# Rocky_Switch_SSR_Shield.net
KiCad netlist of a schematic drawn in EAGLE
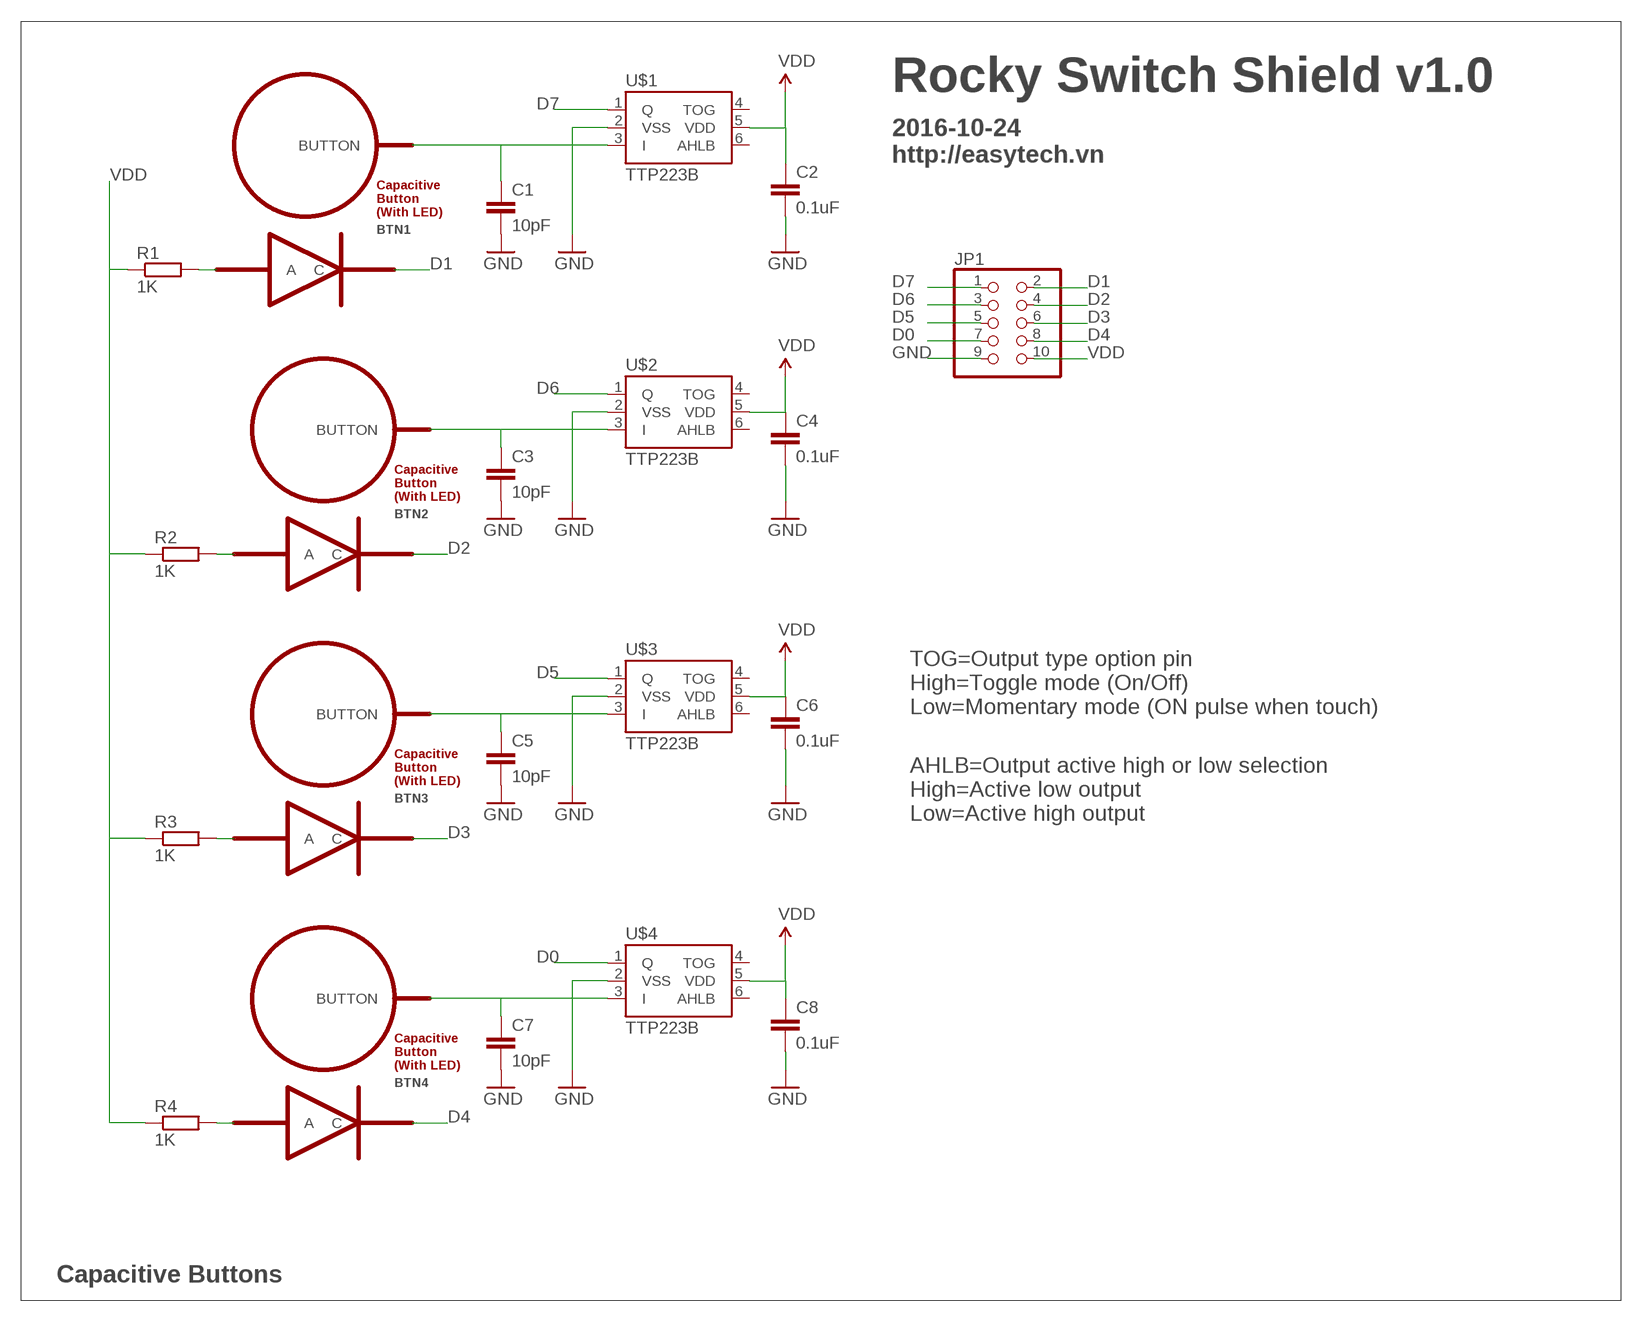
[diagram p0: schematic, sheet 1]

(export (version "E")
  (design (tool "Eeschema 10.0.6"))
  (components
    (comp (ref "BTN1")
      (value "BUTTON_PASSIVE_LED")
      (footprint "eagle-import:BUTTON_PASSIVE_LED")
      (libsource (lib "eagle-import") (part "BUTTON_PASSIVE_LED"))
    )
    (comp (ref "BTN2")
      (value "BUTTON_PASSIVE_LED")
      (footprint "eagle-import:BUTTON_PASSIVE_LED")
      (libsource (lib "eagle-import") (part "BUTTON_PASSIVE_LED"))
    )
    (comp (ref "BTN3")
      (value "BUTTON_PASSIVE_LED")
      (footprint "eagle-import:BUTTON_PASSIVE_LED")
      (libsource (lib "eagle-import") (part "BUTTON_PASSIVE_LED"))
    )
    (comp (ref "BTN4")
      (value "BUTTON_PASSIVE_LED")
      (footprint "eagle-import:BUTTON_PASSIVE_LED")
      (libsource (lib "eagle-import") (part "BUTTON_PASSIVE_LED"))
    )
    (comp (ref "C1")
      (value "10pF")
      (footprint "eagle-import:C0805K")
      (libsource (lib "eagle-import") (part "C-EUC0805K"))
    )
    (comp (ref "C2")
      (value "0.1uF")
      (footprint "eagle-import:C0805K")
      (libsource (lib "eagle-import") (part "C-EUC0805K"))
    )
    (comp (ref "C3")
      (value "10pF")
      (footprint "eagle-import:C0805K")
      (libsource (lib "eagle-import") (part "C-EUC0805K"))
    )
    (comp (ref "C4")
      (value "0.1uF")
      (footprint "eagle-import:C0805K")
      (libsource (lib "eagle-import") (part "C-EUC0805K"))
    )
    (comp (ref "C5")
      (value "10pF")
      (footprint "eagle-import:C0805K")
      (libsource (lib "eagle-import") (part "C-EUC0805K"))
    )
    (comp (ref "C6")
      (value "0.1uF")
      (footprint "eagle-import:C0805K")
      (libsource (lib "eagle-import") (part "C-EUC0805K"))
    )
    (comp (ref "C7")
      (value "10pF")
      (footprint "eagle-import:C0805K")
      (libsource (lib "eagle-import") (part "C-EUC0805K"))
    )
    (comp (ref "C8")
      (value "0.1uF")
      (footprint "eagle-import:C0805K")
      (libsource (lib "eagle-import") (part "C-EUC0805K"))
    )
    (comp (ref "JP1")
      (value "PINHD-2X5")
      (footprint "eagle-import:2X05")
      (libsource (lib "eagle-import") (part "PINHD-2X5"))
    )
    (comp (ref "R1")
      (value "1K")
      (footprint "eagle-import:R0805")
      (libsource (lib "eagle-import") (part "R-EU_R0805"))
    )
    (comp (ref "R2")
      (value "1K")
      (footprint "eagle-import:R0805")
      (libsource (lib "eagle-import") (part "R-EU_R0805"))
    )
    (comp (ref "R3")
      (value "1K")
      (footprint "eagle-import:R0805")
      (libsource (lib "eagle-import") (part "R-EU_R0805"))
    )
    (comp (ref "R4")
      (value "1K")
      (footprint "eagle-import:R0805")
      (libsource (lib "eagle-import") (part "R-EU_R0805"))
    )
    (comp (ref "U$1")
      (value "TTP223B")
      (footprint "eagle-import:SOT23-6")
      (libsource (lib "eagle-import") (part "TTP223B"))
    )
    (comp (ref "U$2")
      (value "TTP223B")
      (footprint "eagle-import:SOT23-6")
      (libsource (lib "eagle-import") (part "TTP223B"))
    )
    (comp (ref "U$3")
      (value "TTP223B")
      (footprint "eagle-import:SOT23-6")
      (libsource (lib "eagle-import") (part "TTP223B"))
    )
    (comp (ref "U$4")
      (value "TTP223B")
      (footprint "eagle-import:SOT23-6")
      (libsource (lib "eagle-import") (part "TTP223B"))
    )
  )
  (nets
    (net (code "1") (name "/D0") (class "Default")
      (node (ref "JP1") (pin "7") (pinfunction "7_7") (pintype "passive"))
      (node (ref "U$4") (pin "1") (pinfunction "Q_1") (pintype "bidirectional"))
    )
    (net (code "2") (name "/D1") (class "Default")
      (node (ref "BTN1") (pin "C") (pinfunction "C_C") (pintype "bidirectional"))
      (node (ref "JP1") (pin "2") (pinfunction "2_2") (pintype "passive"))
    )
    (net (code "3") (name "/D2") (class "Default")
      (node (ref "BTN2") (pin "C") (pinfunction "C_C") (pintype "bidirectional"))
      (node (ref "JP1") (pin "4") (pinfunction "4_4") (pintype "passive"))
    )
    (net (code "4") (name "/D3") (class "Default")
      (node (ref "BTN3") (pin "C") (pinfunction "C_C") (pintype "bidirectional"))
      (node (ref "JP1") (pin "6") (pinfunction "6_6") (pintype "passive"))
    )
    (net (code "5") (name "/D4") (class "Default")
      (node (ref "BTN4") (pin "C") (pinfunction "C_C") (pintype "bidirectional"))
      (node (ref "JP1") (pin "8") (pinfunction "8_8") (pintype "passive"))
    )
    (net (code "6") (name "/D5") (class "Default")
      (node (ref "JP1") (pin "5") (pinfunction "5_5") (pintype "passive"))
      (node (ref "U$3") (pin "1") (pinfunction "Q_1") (pintype "bidirectional"))
    )
    (net (code "7") (name "/D6") (class "Default")
      (node (ref "JP1") (pin "3") (pinfunction "3_3") (pintype "passive"))
      (node (ref "U$2") (pin "1") (pinfunction "Q_1") (pintype "bidirectional"))
    )
    (net (code "8") (name "/D7") (class "Default")
      (node (ref "JP1") (pin "1") (pinfunction "1_1") (pintype "passive"))
      (node (ref "U$1") (pin "1") (pinfunction "Q_1") (pintype "bidirectional"))
    )
    (net (code "9") (name "GND") (class "Default")
      (node (ref "C1") (pin "2") (pinfunction "2_2") (pintype "passive"))
      (node (ref "C2") (pin "2") (pinfunction "2_2") (pintype "passive"))
      (node (ref "C3") (pin "2") (pinfunction "2_2") (pintype "passive"))
      (node (ref "C4") (pin "2") (pinfunction "2_2") (pintype "passive"))
      (node (ref "C5") (pin "2") (pinfunction "2_2") (pintype "passive"))
      (node (ref "C6") (pin "2") (pinfunction "2_2") (pintype "passive"))
      (node (ref "C7") (pin "2") (pinfunction "2_2") (pintype "passive"))
      (node (ref "C8") (pin "2") (pinfunction "2_2") (pintype "passive"))
      (node (ref "JP1") (pin "9") (pinfunction "9_9") (pintype "passive"))
      (node (ref "U$1") (pin "2") (pinfunction "VSS_2") (pintype "bidirectional"))
      (node (ref "U$2") (pin "2") (pinfunction "VSS_2") (pintype "bidirectional"))
      (node (ref "U$3") (pin "2") (pinfunction "VSS_2") (pintype "bidirectional"))
      (node (ref "U$4") (pin "2") (pinfunction "VSS_2") (pintype "bidirectional"))
    )
    (net (code "10") (name "Net-(BTN1-PadA)") (class "Default")
      (node (ref "BTN1") (pin "A") (pinfunction "A_A") (pintype "bidirectional"))
      (node (ref "R1") (pin "2") (pinfunction "2_2") (pintype "passive"))
    )
    (net (code "11") (name "Net-(BTN2-PadA)") (class "Default")
      (node (ref "BTN2") (pin "A") (pinfunction "A_A") (pintype "bidirectional"))
      (node (ref "R2") (pin "2") (pinfunction "2_2") (pintype "passive"))
    )
    (net (code "12") (name "Net-(BTN3-PadA)") (class "Default")
      (node (ref "BTN3") (pin "A") (pinfunction "A_A") (pintype "bidirectional"))
      (node (ref "R3") (pin "2") (pinfunction "2_2") (pintype "passive"))
    )
    (net (code "13") (name "Net-(BTN4-PadA)") (class "Default")
      (node (ref "BTN4") (pin "A") (pinfunction "A_A") (pintype "bidirectional"))
      (node (ref "R4") (pin "2") (pinfunction "2_2") (pintype "passive"))
    )
    (net (code "14") (name "Net-(U$1-I)") (class "Default")
      (node (ref "BTN1") (pin "BUTTON") (pinfunction "BUTTON_BUTTON") (pintype "passive"))
      (node (ref "C1") (pin "1") (pinfunction "1_1") (pintype "passive"))
      (node (ref "U$1") (pin "3") (pinfunction "I_3") (pintype "bidirectional"))
    )
    (net (code "15") (name "Net-(U$2-I)") (class "Default")
      (node (ref "BTN2") (pin "BUTTON") (pinfunction "BUTTON_BUTTON") (pintype "passive"))
      (node (ref "C3") (pin "1") (pinfunction "1_1") (pintype "passive"))
      (node (ref "U$2") (pin "3") (pinfunction "I_3") (pintype "bidirectional"))
    )
    (net (code "16") (name "Net-(U$3-I)") (class "Default")
      (node (ref "BTN3") (pin "BUTTON") (pinfunction "BUTTON_BUTTON") (pintype "passive"))
      (node (ref "C5") (pin "1") (pinfunction "1_1") (pintype "passive"))
      (node (ref "U$3") (pin "3") (pinfunction "I_3") (pintype "bidirectional"))
    )
    (net (code "17") (name "Net-(U$4-I)") (class "Default")
      (node (ref "BTN4") (pin "BUTTON") (pinfunction "BUTTON_BUTTON") (pintype "passive"))
      (node (ref "C7") (pin "1") (pinfunction "1_1") (pintype "passive"))
      (node (ref "U$4") (pin "3") (pinfunction "I_3") (pintype "bidirectional"))
    )
    (net (code "18") (name "VDD") (class "Default")
      (node (ref "C2") (pin "1") (pinfunction "1_1") (pintype "passive"))
      (node (ref "C4") (pin "1") (pinfunction "1_1") (pintype "passive"))
      (node (ref "C6") (pin "1") (pinfunction "1_1") (pintype "passive"))
      (node (ref "C8") (pin "1") (pinfunction "1_1") (pintype "passive"))
      (node (ref "JP1") (pin "10") (pinfunction "10_10") (pintype "passive"))
      (node (ref "R1") (pin "1") (pinfunction "1_1") (pintype "passive"))
      (node (ref "R2") (pin "1") (pinfunction "1_1") (pintype "passive"))
      (node (ref "R3") (pin "1") (pinfunction "1_1") (pintype "passive"))
      (node (ref "R4") (pin "1") (pinfunction "1_1") (pintype "passive"))
      (node (ref "U$1") (pin "5") (pinfunction "VDD_5") (pintype "bidirectional"))
      (node (ref "U$2") (pin "5") (pinfunction "VDD_5") (pintype "bidirectional"))
      (node (ref "U$3") (pin "5") (pinfunction "VDD_5") (pintype "bidirectional"))
      (node (ref "U$4") (pin "5") (pinfunction "VDD_5") (pintype "bidirectional"))
    )
    (net (code "19") (name "unconnected-(U$1-AHLB-Pad6)") (class "Default")
      (node (ref "U$1") (pin "6") (pinfunction "AHLB_6") (pintype "bidirectional"))
    )
    (net (code "20") (name "unconnected-(U$1-TOG-Pad4)") (class "Default")
      (node (ref "U$1") (pin "4") (pinfunction "TOG_4") (pintype "bidirectional"))
    )
    (net (code "21") (name "unconnected-(U$2-AHLB-Pad6)") (class "Default")
      (node (ref "U$2") (pin "6") (pinfunction "AHLB_6") (pintype "bidirectional"))
    )
    (net (code "22") (name "unconnected-(U$2-TOG-Pad4)") (class "Default")
      (node (ref "U$2") (pin "4") (pinfunction "TOG_4") (pintype "bidirectional"))
    )
    (net (code "23") (name "unconnected-(U$3-AHLB-Pad6)") (class "Default")
      (node (ref "U$3") (pin "6") (pinfunction "AHLB_6") (pintype "bidirectional"))
    )
    (net (code "24") (name "unconnected-(U$3-TOG-Pad4)") (class "Default")
      (node (ref "U$3") (pin "4") (pinfunction "TOG_4") (pintype "bidirectional"))
    )
    (net (code "25") (name "unconnected-(U$4-AHLB-Pad6)") (class "Default")
      (node (ref "U$4") (pin "6") (pinfunction "AHLB_6") (pintype "bidirectional"))
    )
    (net (code "26") (name "unconnected-(U$4-TOG-Pad4)") (class "Default")
      (node (ref "U$4") (pin "4") (pinfunction "TOG_4") (pintype "bidirectional"))
    )
  )
)
